# USB_mini.net
KiCad netlist of a schematic drawn in Altium Designer
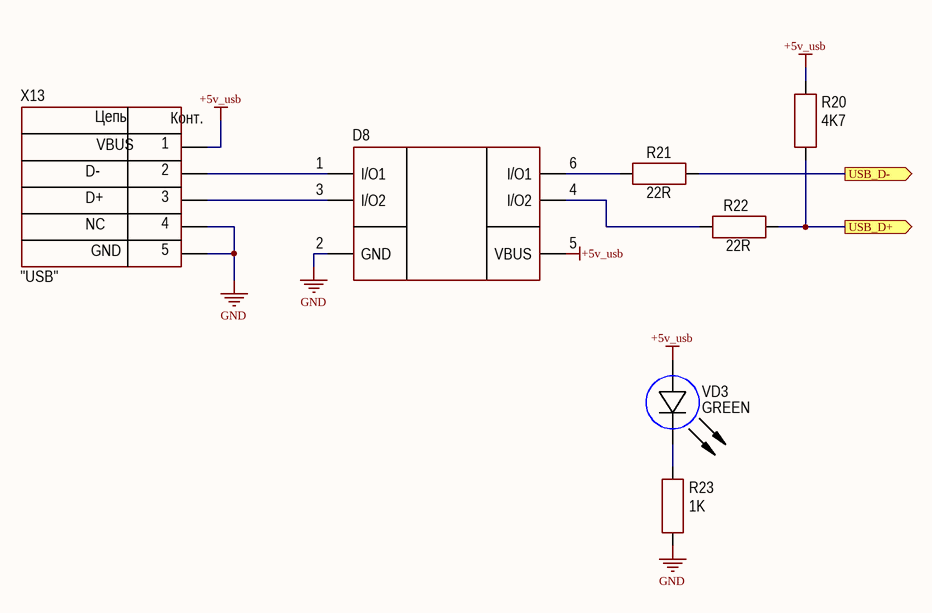
[diagram p0: USB_mini.SchDoc]

(export (version "E")
  (design (tool "Eeschema 10.0.6"))
  (components
    (comp (ref "D8")
      (value "~")
      (footprint "StandardCase:SOT23-6")
      (fields
        (field (name "MANUFACTURER") "STMicroelectronics")
        (field (name "VALUEMANUFACTURERPARTNUMBER") "USB protection, , 5A peak, 17V, Power line, SOT-23-6, -40...+125°C")
        (field (name "PARTNUMBER") "USBLC6-2SC6")
      )
      (libsource (lib "Diode") (part "USBLC6-2SC6"))
    )
    (comp (ref "R20")
      (value "4K7")
      (footprint "StandardCase:RES: 1206")
      (fields
        (field (name "MANUFACTURER") "Yageo")
        (field (name "PARTNUMBER") "RC1206JR-07100RL")
        (field (name "VALUEMANUFACTURERPARTNUMBER") "Resistor film, 4K7, ±5%, 1206, 0.25W, -55...+125°C")
      )
      (libsource (lib "") (part "Resistor_1206_1"))
    )
    (comp (ref "R21")
      (value "22R")
      (footprint "StandardCase:RES: 1206")
      (fields
        (field (name "MANUFACTURER") "Yageo")
        (field (name "PARTNUMBER") "RC1206JR-07100RL")
        (field (name "VALUEMANUFACTURERPARTNUMBER") "Resistor film, 22R, ±5%, 1206, 0.25W, -55...+125°C")
      )
      (libsource (lib "Resistor") (part "Resistor_1206"))
    )
    (comp (ref "R22")
      (value "22R")
      (footprint "StandardCase:RES: 1206")
      (fields
        (field (name "MANUFACTURER") "Yageo")
        (field (name "PARTNUMBER") "RC1206JR-07100RL")
        (field (name "VALUEMANUFACTURERPARTNUMBER") "Resistor film, 22R, ±5%, 1206, 0.25W, -55...+125°C")
      )
      (libsource (lib "Resistor") (part "Resistor_1206"))
    )
    (comp (ref "R23")
      (value "1K")
      (footprint "StandardCase:RES: 1206")
      (fields
        (field (name "MANUFACTURER") "Yageo")
        (field (name "PARTNUMBER") "RC1206JR-07100RL")
        (field (name "VALUEMANUFACTURERPARTNUMBER") "Resistor film, 1K, ±5%, 1206, 0.25W, -55...+125°C")
      )
      (libsource (lib "") (part "Resistor_1206_2"))
    )
    (comp (ref "VD3")
      (value "~")
      (footprint "StandardCase:LED: 1206G")
      (fields
        (field (name "VALUEMANUFACTURERPARTNUMBER") "LED, Green, *, *, *, -55...+150°C")
        (field (name "COLOR") "GREEN")
      )
      (libsource (lib "Diode") (part "LED_single"))
    )
    (comp (ref "X13")
      (value "~")
      (footprint "CustomCase:CON: 0675031020")
      (fields
        (field (name "MANUFACTURER") "Molex")
        (field (name "VALUEMANUFACTURERPARTNUMBER") "USB mini B")
        (field (name "PARTNUMBER") "0675031020")
        (field (name "COMMENTTEXT") "\"USB\"")
      )
      (libsource (lib "Connector") (part "Connector_USB_mini_B"))
    )
  )
  (nets
    (net (code "1") (name "+5v_usb") (class "Default")
      (node (ref "D8") (pin "5") (pinfunction "VBUS_5") (pintype "passive"))
      (node (ref "R20") (pin "1") (pinfunction "1_1") (pintype "passive"))
      (node (ref "VD3") (pin "1") (pinfunction "A_1") (pintype "passive"))
      (node (ref "X13") (pin "1") (pintype "passive"))
    )
    (net (code "2") (name "/USB_D+") (class "Default")
      (node (ref "R20") (pin "2") (pinfunction "2_2") (pintype "passive"))
      (node (ref "R22") (pin "2") (pinfunction "2_2") (pintype "passive"))
    )
    (net (code "3") (name "/USB_D-") (class "Default")
      (node (ref "R21") (pin "2") (pinfunction "2_2") (pintype "passive"))
    )
    (net (code "4") (name "GND") (class "Default")
      (node (ref "D8") (pin "2") (pinfunction "GND_2") (pintype "passive"))
      (node (ref "R23") (pin "1") (pinfunction "1_1") (pintype "passive"))
      (node (ref "X13") (pin "4") (pinfunction "4_4") (pintype "passive"))
      (node (ref "X13") (pin "5") (pinfunction "5_5") (pintype "passive"))
    )
    (net (code "5") (name "Net-(D8-I{slash}O1-Pad1)") (class "Default")
      (node (ref "D8") (pin "1") (pinfunction "I/O1_1") (pintype "passive"))
      (node (ref "X13") (pin "2") (pinfunction "2_2") (pintype "passive"))
    )
    (net (code "6") (name "Net-(D8-I{slash}O1-Pad6)") (class "Default")
      (node (ref "D8") (pin "6") (pinfunction "I/O1_6") (pintype "passive"))
      (node (ref "R21") (pin "1") (pinfunction "1_1") (pintype "passive"))
    )
    (net (code "7") (name "Net-(D8-I{slash}O2-Pad3)") (class "Default")
      (node (ref "D8") (pin "3") (pinfunction "I/O2_3") (pintype "passive"))
      (node (ref "X13") (pin "3") (pinfunction "3_3") (pintype "passive"))
    )
    (net (code "8") (name "Net-(D8-I{slash}O2-Pad4)") (class "Default")
      (node (ref "D8") (pin "4") (pinfunction "I/O2_4") (pintype "passive"))
      (node (ref "R22") (pin "1") (pinfunction "1_1") (pintype "passive"))
    )
    (net (code "9") (name "Net-(VD3-C)") (class "Default")
      (node (ref "R23") (pin "2") (pinfunction "2_2") (pintype "passive"))
      (node (ref "VD3") (pin "2") (pinfunction "C_2") (pintype "passive"))
    )
  )
)
